# schematic.net
KiCad netlist of a schematic drawn in EasyEDA
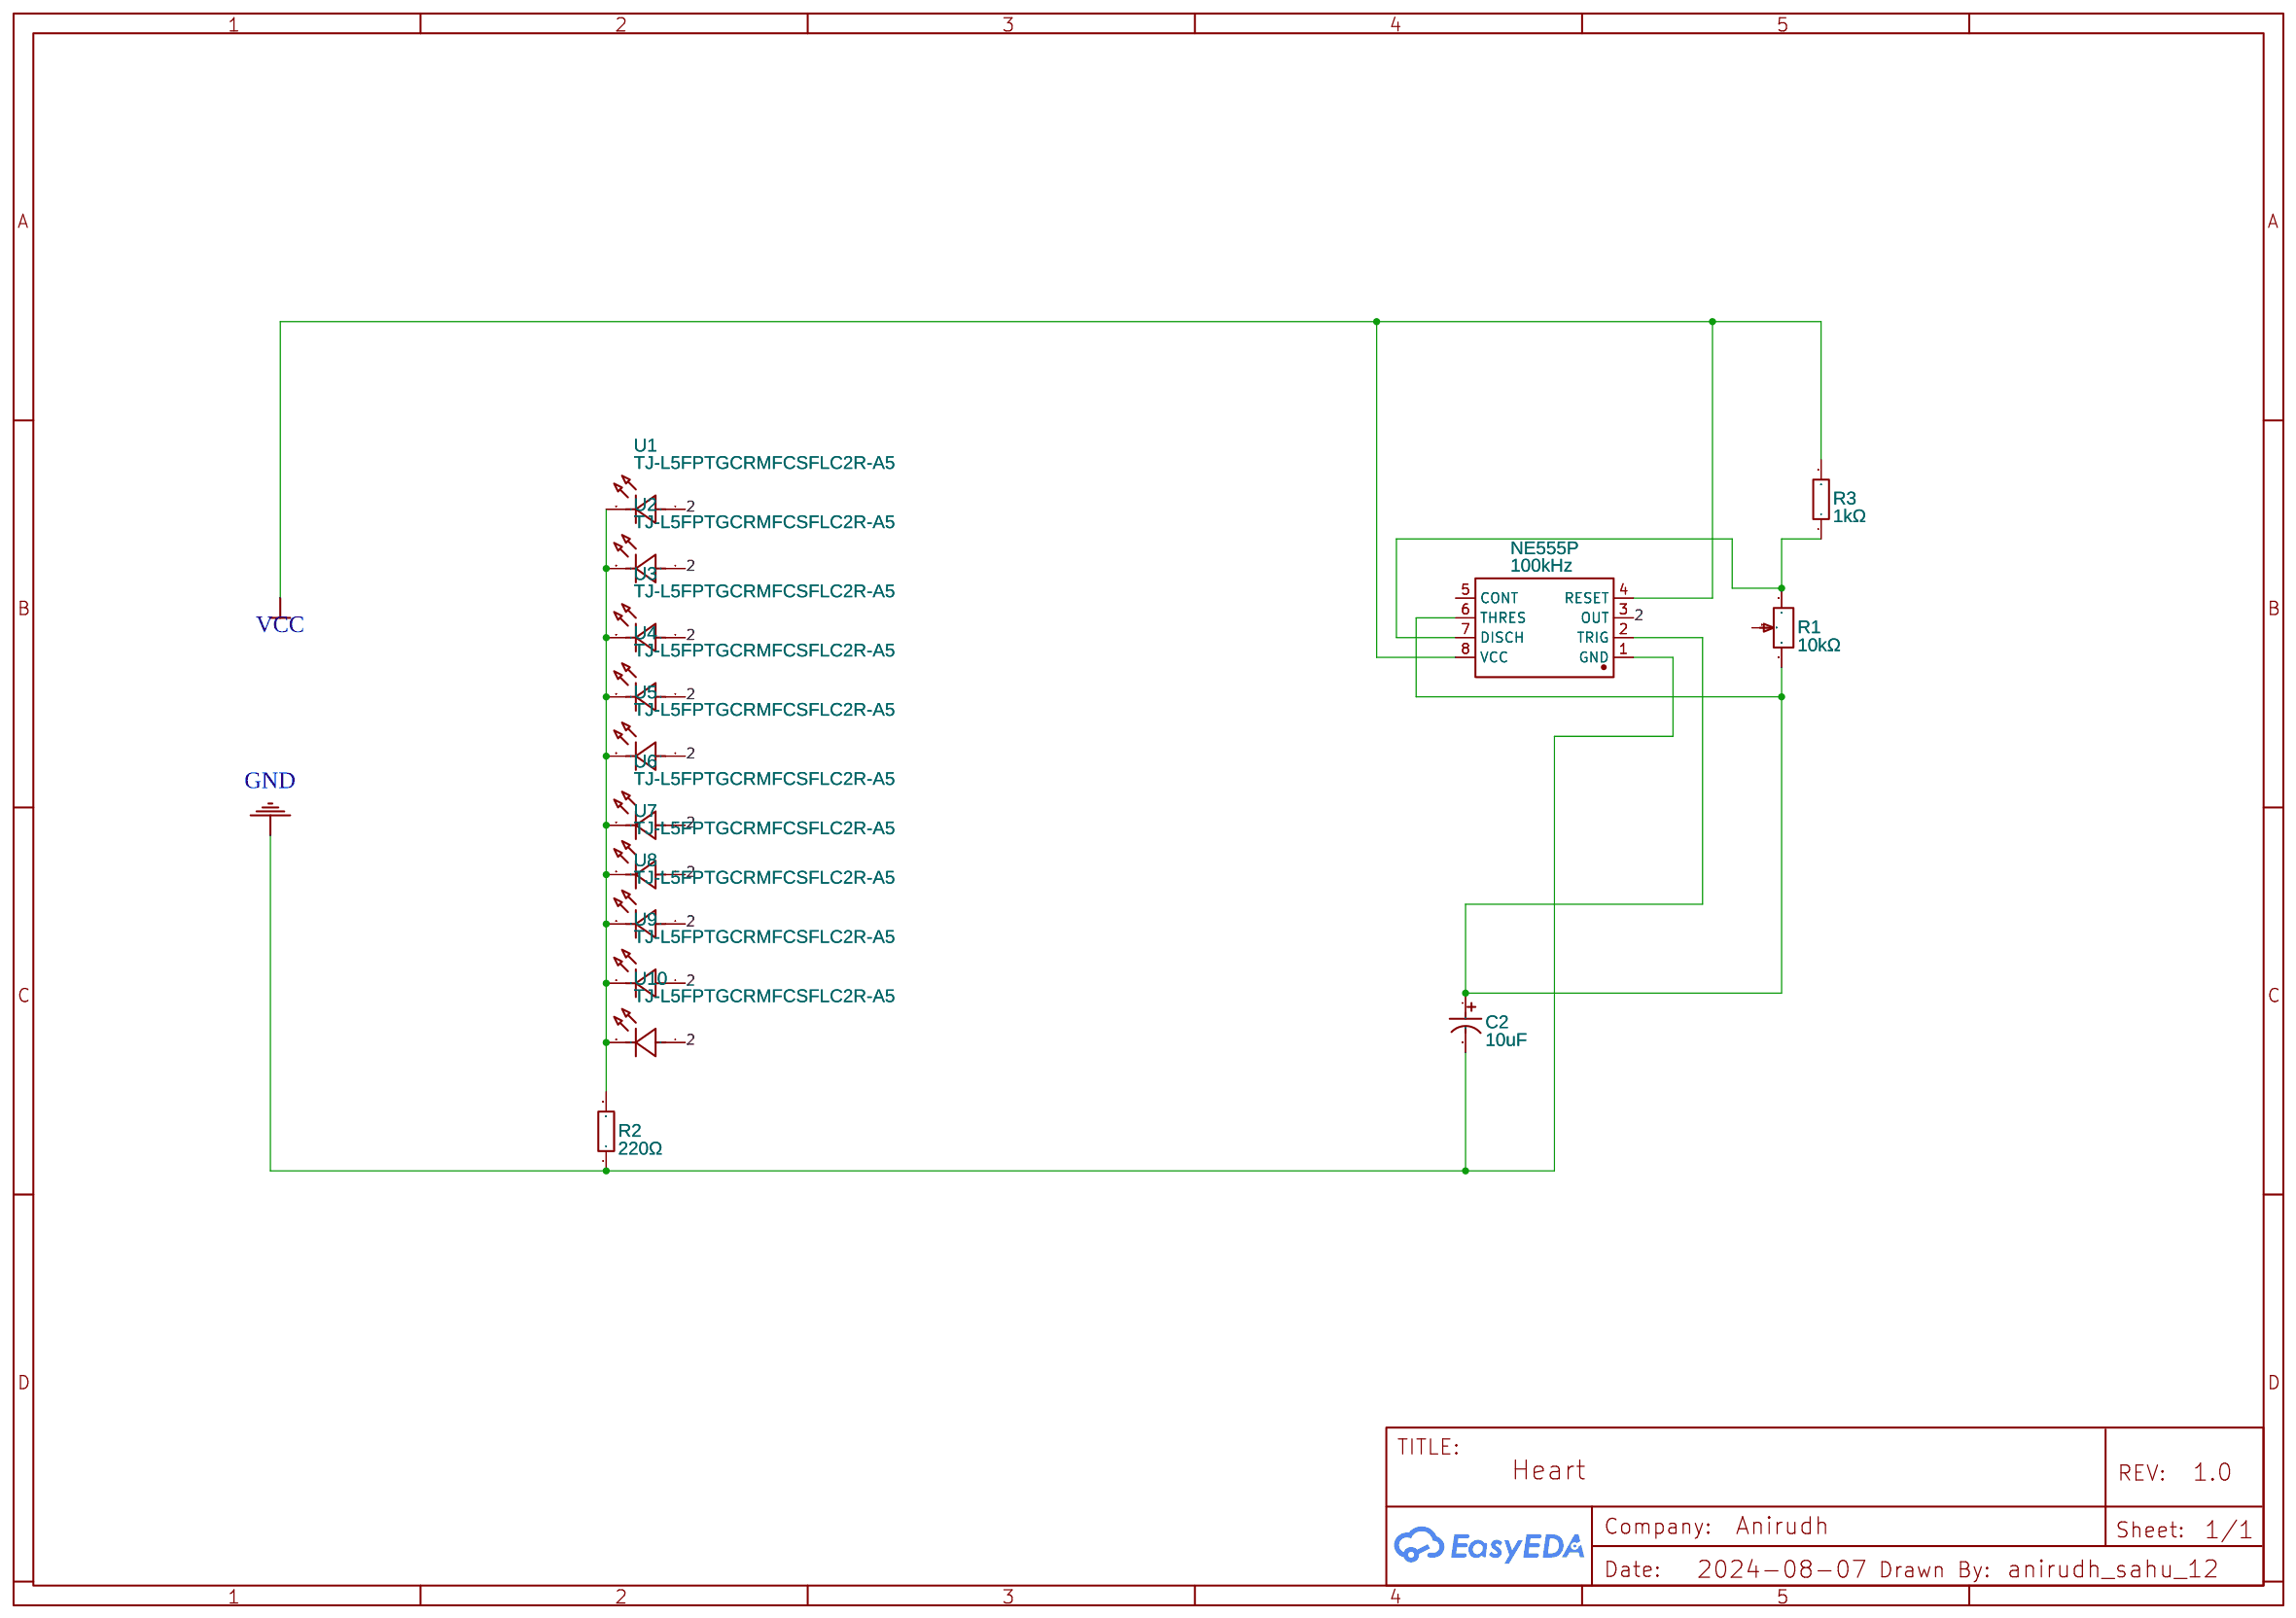
[diagram p0: schematic sheet]

(export (version "E")
  (design (tool "Eeschema 10.0.6"))
  (components
    (comp (ref "C2")
      (value "10uF")
      (fields (field (name "Manufacturer Part") "RVT1H100M0605") (field (name "Manufacturer") "ROQANG(容强)"))
      (libsource (lib "") (part "RVT1H100M0605"))
    )
    (comp (ref "NE555P")
      (value "100kHz")
      (fields (field (name "Manufacturer Part") "NE555P") (field (name "Manufacturer") "TI(德州仪器)"))
      (libsource (lib "") (part "NE555P"))
    )
    (comp (ref "R1")
      (value "10kΩ")
      (fields (field (name "Manufacturer Part") "3296W-1-103LF") (field (name "Manufacturer") "BOURNS"))
      (libsource (lib "") (part "3296W-1-103LF"))
    )
    (comp (ref "R2")
      (value "220Ω")
      (fields
        (field (name "Manufacturer Part") "MFR02SF2200A10")
        (field (name "Manufacturer") "UNI-ROYAL(厚声)")
      )
      (libsource (lib "") (part "MFR02SF2200A10"))
    )
    (comp (ref "R3")
      (value "1kΩ")
      (fields
        (field (name "Manufacturer Part") "MFR01SF1001A10")
        (field (name "Manufacturer") "UNI-ROYAL(厚声)")
      )
      (libsource (lib "") (part "MFR01SF1001A10"))
    )
    (comp (ref "U1")
      (value "TJ-L5FPTGCRMFCSFLC2R-A5")
      (fields (field (name "Manufacturer") "TOGIALED(统佳)"))
      (libsource (lib "") (part "TJ-L5FPTGCRMFCSFLC2R-A5"))
    )
    (comp (ref "U2")
      (value "TJ-L5FPTGCRMFCSFLC2R-A5")
      (fields (field (name "Manufacturer") "TOGIALED(统佳)"))
      (libsource (lib "") (part "TJ-L5FPTGCRMFCSFLC2R-A5"))
    )
    (comp (ref "U3")
      (value "TJ-L5FPTGCRMFCSFLC2R-A5")
      (fields (field (name "Manufacturer") "TOGIALED(统佳)"))
      (libsource (lib "") (part "TJ-L5FPTGCRMFCSFLC2R-A5"))
    )
    (comp (ref "U4")
      (value "TJ-L5FPTGCRMFCSFLC2R-A5")
      (fields (field (name "Manufacturer") "TOGIALED(统佳)"))
      (libsource (lib "") (part "TJ-L5FPTGCRMFCSFLC2R-A5"))
    )
    (comp (ref "U5")
      (value "TJ-L5FPTGCRMFCSFLC2R-A5")
      (fields (field (name "Manufacturer") "TOGIALED(统佳)"))
      (libsource (lib "") (part "TJ-L5FPTGCRMFCSFLC2R-A5"))
    )
    (comp (ref "U6")
      (value "TJ-L5FPTGCRMFCSFLC2R-A5")
      (fields (field (name "Manufacturer") "TOGIALED(统佳)"))
      (libsource (lib "") (part "TJ-L5FPTGCRMFCSFLC2R-A5"))
    )
    (comp (ref "U7")
      (value "TJ-L5FPTGCRMFCSFLC2R-A5")
      (fields (field (name "Manufacturer") "TOGIALED(统佳)"))
      (libsource (lib "") (part "TJ-L5FPTGCRMFCSFLC2R-A5"))
    )
    (comp (ref "U8")
      (value "TJ-L5FPTGCRMFCSFLC2R-A5")
      (fields (field (name "Manufacturer") "TOGIALED(统佳)"))
      (libsource (lib "") (part "TJ-L5FPTGCRMFCSFLC2R-A5"))
    )
    (comp (ref "U9")
      (value "TJ-L5FPTGCRMFCSFLC2R-A5")
      (fields (field (name "Manufacturer") "TOGIALED(统佳)"))
      (libsource (lib "") (part "TJ-L5FPTGCRMFCSFLC2R-A5"))
    )
    (comp (ref "U10")
      (value "TJ-L5FPTGCRMFCSFLC2R-A5")
      (fields (field (name "Manufacturer") "TOGIALED(统佳)"))
      (libsource (lib "") (part "TJ-L5FPTGCRMFCSFLC2R-A5"))
    )
  )
  (nets
    (net (code "1") (name "/2") (class "Default")
      (node (ref "NE555P") (pin "3") (pinfunction "OUT_3") (pintype "unspecified"))
      (node (ref "U1") (pin "1") (pinfunction "A_1") (pintype "unspecified"))
      (node (ref "U10") (pin "1") (pinfunction "A_1") (pintype "unspecified"))
      (node (ref "U2") (pin "1") (pinfunction "A_1") (pintype "unspecified"))
      (node (ref "U3") (pin "1") (pinfunction "A_1") (pintype "unspecified"))
      (node (ref "U4") (pin "1") (pinfunction "A_1") (pintype "unspecified"))
      (node (ref "U5") (pin "1") (pinfunction "A_1") (pintype "unspecified"))
      (node (ref "U6") (pin "1") (pinfunction "A_1") (pintype "unspecified"))
      (node (ref "U7") (pin "1") (pinfunction "A_1") (pintype "unspecified"))
      (node (ref "U8") (pin "1") (pinfunction "A_1") (pintype "unspecified"))
      (node (ref "U9") (pin "1") (pinfunction "A_1") (pintype "unspecified"))
    )
    (net (code "2") (name "GND") (class "Default")
      (node (ref "C2") (pin "2") (pinfunction "2_2") (pintype "input"))
      (node (ref "NE555P") (pin "1") (pinfunction "GND_1") (pintype "unspecified"))
      (node (ref "R2") (pin "1") (pinfunction "1_1") (pintype "input"))
    )
    (net (code "3") (name "Net-(NE555P-DISCH)") (class "Default")
      (node (ref "NE555P") (pin "7") (pinfunction "DISCH_7") (pintype "unspecified"))
      (node (ref "R1") (pin "1") (pinfunction "1_1") (pintype "input"))
      (node (ref "R3") (pin "1") (pinfunction "1_1") (pintype "input"))
    )
    (net (code "4") (name "Net-(NE555P-THRES)") (class "Default")
      (node (ref "C2") (pin "1") (pinfunction "1_1") (pintype "input"))
      (node (ref "NE555P") (pin "2") (pinfunction "TRIG_2") (pintype "unspecified"))
      (node (ref "NE555P") (pin "6") (pinfunction "THRES_6") (pintype "unspecified"))
      (node (ref "R1") (pin "3") (pinfunction "3_3") (pintype "input"))
    )
    (net (code "5") (name "Net-(U1-K)") (class "Default")
      (node (ref "R2") (pin "2") (pinfunction "2_2") (pintype "input"))
      (node (ref "U1") (pin "2") (pinfunction "K_2") (pintype "unspecified"))
      (node (ref "U10") (pin "2") (pinfunction "K_2") (pintype "unspecified"))
      (node (ref "U2") (pin "2") (pinfunction "K_2") (pintype "unspecified"))
      (node (ref "U3") (pin "2") (pinfunction "K_2") (pintype "unspecified"))
      (node (ref "U4") (pin "2") (pinfunction "K_2") (pintype "unspecified"))
      (node (ref "U5") (pin "2") (pinfunction "K_2") (pintype "unspecified"))
      (node (ref "U6") (pin "2") (pinfunction "K_2") (pintype "unspecified"))
      (node (ref "U7") (pin "2") (pinfunction "K_2") (pintype "unspecified"))
      (node (ref "U8") (pin "2") (pinfunction "K_2") (pintype "unspecified"))
      (node (ref "U9") (pin "2") (pinfunction "K_2") (pintype "unspecified"))
    )
    (net (code "6") (name "VCC") (class "Default")
      (node (ref "NE555P") (pin "4") (pinfunction "RESET_4") (pintype "unspecified"))
      (node (ref "NE555P") (pin "8") (pinfunction "VCC_8") (pintype "unspecified"))
      (node (ref "R3") (pin "2") (pinfunction "2_2") (pintype "input"))
    )
    (net (code "7") (name "unconnected-(NE555P-CONT-Pad5)") (class "Default")
      (node (ref "NE555P") (pin "5") (pinfunction "CONT_5") (pintype "unspecified"))
    )
    (net (code "8") (name "unconnected-(R1-Pad2)") (class "Default")
      (node (ref "R1") (pin "2") (pinfunction "2_2") (pintype "input"))
    )
  )
)
